# I2C_system.net
KiCad netlist of a schematic drawn in Altium Designer
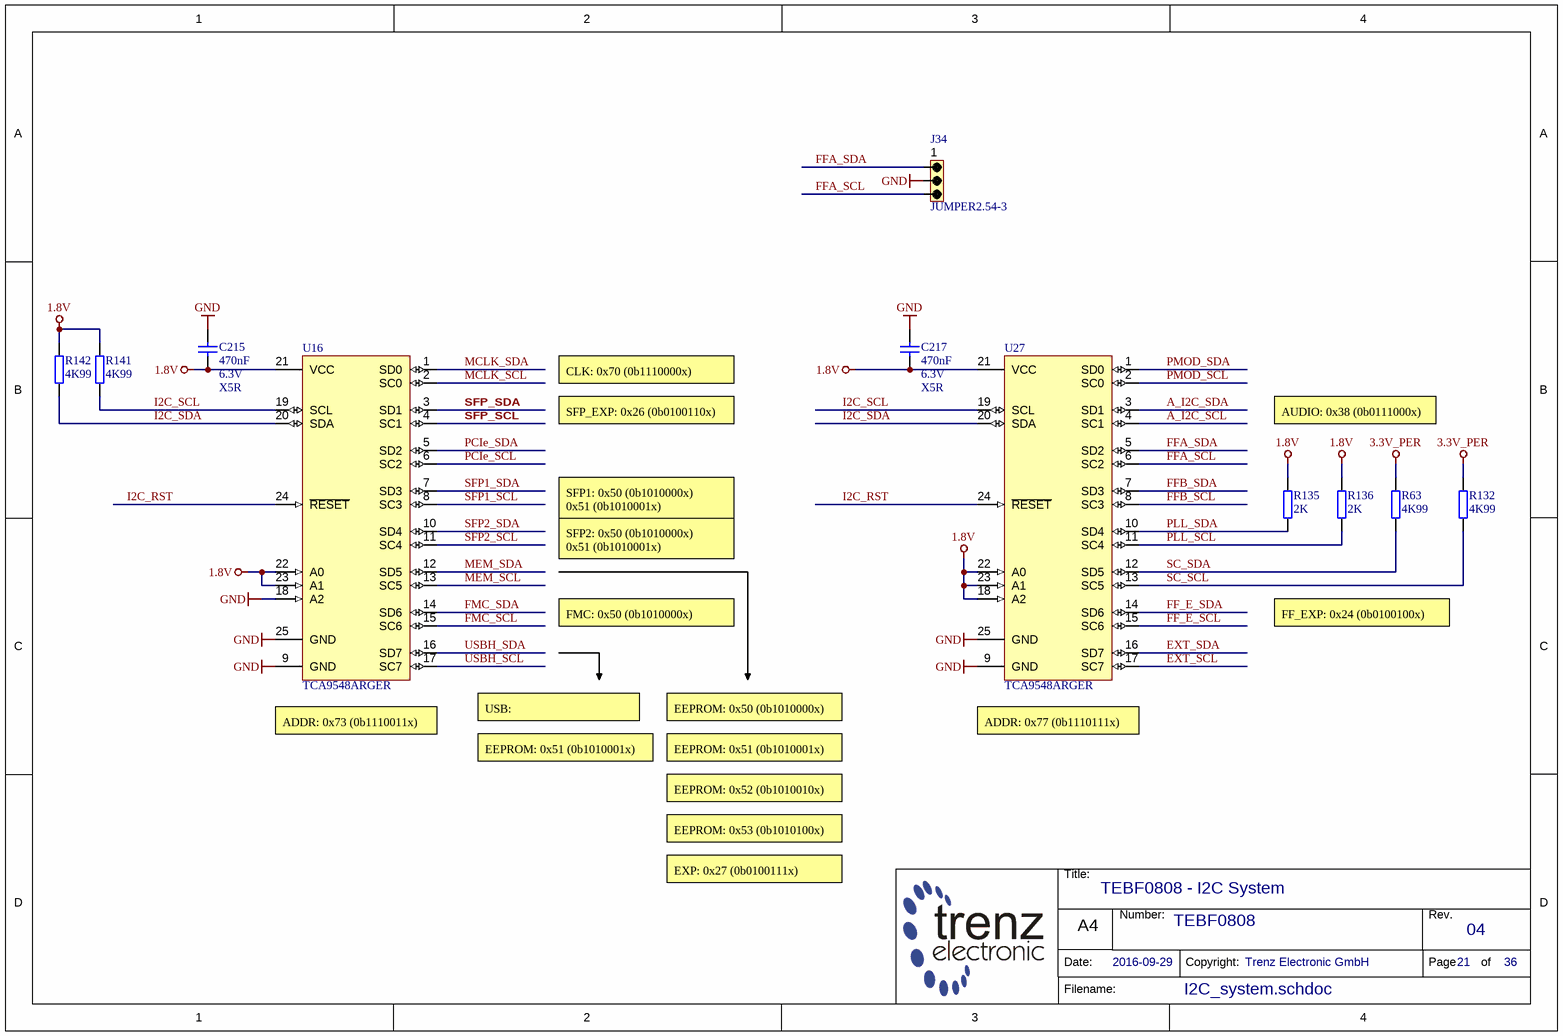
[diagram p0: I2C_system.schdoc]

(export (version "E")
  (design (tool "Eeschema 10.0.6"))
  (components
    (comp (ref "C215")
      (value "470nF")
      (footprint "CAPC1005X55N")
      (description "KON 470nF 6,3V X5R SMD")
      (fields (field (name "VOLTAGE") "6.3V") (field (name "TECHNOLOGY") "X5R"))
      (libsource (lib "TE") (part "CAP-NP"))
    )
    (comp (ref "C217")
      (value "470nF")
      (footprint "CAPC1005X55N")
      (description "KON 470nF 6,3V X5R SMD")
      (fields (field (name "VOLTAGE") "6.3V") (field (name "TECHNOLOGY") "X5R"))
      (libsource (lib "TE") (part "CAP-NP"))
    )
    (comp (ref "J34")
      (value "JUMPER2.54-3")
      (footprint "JUMPER2_54-3")
      (description "Stiftleiste gerade 1-reihig, 3pol.")
      (libsource (lib "TE") (part "JUMPER2.54-3"))
    )
    (comp (ref "R63")
      (value "4K99")
      (footprint "RESC1005X40N")
      (description "WID SMD 4K99 1% 0,063W")
      (fields (field (name "TOLERANCE") "1%"))
      (libsource (lib "TE") (part "RES"))
    )
    (comp (ref "R132")
      (value "4K99")
      (footprint "RESC1005X40N")
      (description "WID SMD 4K99 1% 0,063W")
      (fields (field (name "TOLERANCE") "1%"))
      (libsource (lib "TE") (part "RES"))
    )
    (comp (ref "R135")
      (value "2K")
      (footprint "RESC1005X40N")
      (description "WID SMD 2K 1% 0,063W")
      (fields (field (name "TOLERANCE") "1%"))
      (libsource (lib "TE") (part "RES"))
    )
    (comp (ref "R136")
      (value "2K")
      (footprint "RESC1005X40N")
      (description "WID SMD 2K 1% 0,063W")
      (fields (field (name "TOLERANCE") "1%"))
      (libsource (lib "TE") (part "RES"))
    )
    (comp (ref "R141")
      (value "4K99")
      (footprint "RESC1005X40N")
      (description "WID SMD 4K99 1% 0,063W")
      (fields (field (name "TOLERANCE") "1%"))
      (libsource (lib "TE") (part "RES"))
    )
    (comp (ref "R142")
      (value "4K99")
      (footprint "RESC1005X40N")
      (description "WID SMD 4K99 1% 0,063W")
      (fields (field (name "TOLERANCE") "1%"))
      (libsource (lib "TE") (part "RES"))
    )
    (comp (ref "U16")
      (value "TCA9548ARGER")
      (footprint "QFN50P400X400X100-25N-220")
      (libsource (lib "TE") (part "TCA9548ARGER"))
    )
    (comp (ref "U27")
      (value "TCA9548ARGER")
      (footprint "QFN50P400X400X100-25N-220")
      (libsource (lib "TE") (part "TCA9548ARGER"))
    )
  )
  (nets
    (net (code "1") (name "/A_I2C_SCL") (class "Default")
      (node (ref "U27") (pin "4") (pinfunction "SC1_4") (pintype "bidirectional"))
    )
    (net (code "2") (name "/A_I2C_SDA") (class "Default")
      (node (ref "U27") (pin "3") (pinfunction "SD1_3") (pintype "bidirectional"))
    )
    (net (code "3") (name "/EXT_SCL") (class "Default")
      (node (ref "U27") (pin "17") (pinfunction "SC7_17") (pintype "bidirectional"))
    )
    (net (code "4") (name "/EXT_SDA") (class "Default")
      (node (ref "U27") (pin "16") (pinfunction "SD7_16") (pintype "bidirectional"))
    )
    (net (code "5") (name "/FFA_SCL") (class "Default")
      (node (ref "J34") (pin "3") (pinfunction "3_3") (pintype "passive"))
      (node (ref "U27") (pin "6") (pinfunction "SC2_6") (pintype "bidirectional"))
    )
    (net (code "6") (name "/FFA_SDA") (class "Default")
      (node (ref "J34") (pin "1") (pinfunction "1_1") (pintype "passive"))
      (node (ref "U27") (pin "5") (pinfunction "SD2_5") (pintype "bidirectional"))
    )
    (net (code "7") (name "/FFB_SCL") (class "Default")
      (node (ref "U27") (pin "8") (pinfunction "SC3_8") (pintype "bidirectional"))
    )
    (net (code "8") (name "/FFB_SDA") (class "Default")
      (node (ref "U27") (pin "7") (pinfunction "SD3_7") (pintype "bidirectional"))
    )
    (net (code "9") (name "/FF_E_SCL") (class "Default")
      (node (ref "U27") (pin "15") (pinfunction "SC6_15") (pintype "bidirectional"))
    )
    (net (code "10") (name "/FF_E_SDA") (class "Default")
      (node (ref "U27") (pin "14") (pinfunction "SD6_14") (pintype "bidirectional"))
    )
    (net (code "11") (name "/FMC_SCL") (class "Default")
      (node (ref "U16") (pin "15") (pinfunction "SC6_15") (pintype "bidirectional"))
    )
    (net (code "12") (name "/FMC_SDA") (class "Default")
      (node (ref "U16") (pin "14") (pinfunction "SD6_14") (pintype "bidirectional"))
    )
    (net (code "13") (name "/I2C_RST") (class "Default")
      (node (ref "U16") (pin "24") (pinfunction "~{RESET}_24") (pintype "input"))
      (node (ref "U27") (pin "24") (pinfunction "~{RESET}_24") (pintype "input"))
    )
    (net (code "14") (name "/I2C_SCL") (class "Default")
      (node (ref "R141") (pin "2") (pinfunction "2_2") (pintype "passive"))
      (node (ref "U16") (pin "19") (pinfunction "SCL_19") (pintype "bidirectional"))
      (node (ref "U27") (pin "19") (pinfunction "SCL_19") (pintype "bidirectional"))
    )
    (net (code "15") (name "/I2C_SDA") (class "Default")
      (node (ref "R142") (pin "2") (pinfunction "2_2") (pintype "passive"))
      (node (ref "U16") (pin "20") (pinfunction "SDA_20") (pintype "bidirectional"))
      (node (ref "U27") (pin "20") (pinfunction "SDA_20") (pintype "bidirectional"))
    )
    (net (code "16") (name "/MCLK_SCL") (class "Default")
      (node (ref "U16") (pin "2") (pinfunction "SC0_2") (pintype "bidirectional"))
    )
    (net (code "17") (name "/MCLK_SDA") (class "Default")
      (node (ref "U16") (pin "1") (pinfunction "SD0_1") (pintype "bidirectional"))
    )
    (net (code "18") (name "/MEM_SCL") (class "Default")
      (node (ref "U16") (pin "13") (pinfunction "SC5_13") (pintype "bidirectional"))
    )
    (net (code "19") (name "/MEM_SDA") (class "Default")
      (node (ref "U16") (pin "12") (pinfunction "SD5_12") (pintype "bidirectional"))
    )
    (net (code "20") (name "/PCIe_SCL") (class "Default")
      (node (ref "U16") (pin "6") (pinfunction "SC2_6") (pintype "bidirectional"))
    )
    (net (code "21") (name "/PCIe_SDA") (class "Default")
      (node (ref "U16") (pin "5") (pinfunction "SD2_5") (pintype "bidirectional"))
    )
    (net (code "22") (name "/PLL_SCL") (class "Default")
      (node (ref "R136") (pin "1") (pinfunction "1_1") (pintype "passive"))
      (node (ref "U27") (pin "11") (pinfunction "SC4_11") (pintype "bidirectional"))
    )
    (net (code "23") (name "/PLL_SDA") (class "Default")
      (node (ref "R135") (pin "1") (pinfunction "1_1") (pintype "passive"))
      (node (ref "U27") (pin "10") (pinfunction "SD4_10") (pintype "bidirectional"))
    )
    (net (code "24") (name "/PMOD_SCL") (class "Default")
      (node (ref "U27") (pin "2") (pinfunction "SC0_2") (pintype "bidirectional"))
    )
    (net (code "25") (name "/PMOD_SDA") (class "Default")
      (node (ref "U27") (pin "1") (pinfunction "SD0_1") (pintype "bidirectional"))
    )
    (net (code "26") (name "/SC_SCL") (class "Default")
      (node (ref "R132") (pin "2") (pinfunction "2_2") (pintype "passive"))
      (node (ref "U27") (pin "13") (pinfunction "SC5_13") (pintype "bidirectional"))
    )
    (net (code "27") (name "/SC_SDA") (class "Default")
      (node (ref "R63") (pin "2") (pinfunction "2_2") (pintype "passive"))
      (node (ref "U27") (pin "12") (pinfunction "SD5_12") (pintype "bidirectional"))
    )
    (net (code "28") (name "/SFP1_SCL") (class "Default")
      (node (ref "U16") (pin "8") (pinfunction "SC3_8") (pintype "bidirectional"))
    )
    (net (code "29") (name "/SFP1_SDA") (class "Default")
      (node (ref "U16") (pin "7") (pinfunction "SD3_7") (pintype "bidirectional"))
    )
    (net (code "30") (name "/SFP2_SCL") (class "Default")
      (node (ref "U16") (pin "11") (pinfunction "SC4_11") (pintype "bidirectional"))
    )
    (net (code "31") (name "/SFP2_SDA") (class "Default")
      (node (ref "U16") (pin "10") (pinfunction "SD4_10") (pintype "bidirectional"))
    )
    (net (code "32") (name "/SFP_SCL") (class "Default")
      (node (ref "U16") (pin "4") (pinfunction "SC1_4") (pintype "bidirectional"))
    )
    (net (code "33") (name "/SFP_SDA") (class "Default")
      (node (ref "U16") (pin "3") (pinfunction "SD1_3") (pintype "bidirectional"))
    )
    (net (code "34") (name "/USBH_SCL") (class "Default")
      (node (ref "U16") (pin "17") (pinfunction "SC7_17") (pintype "bidirectional"))
    )
    (net (code "35") (name "/USBH_SDA") (class "Default")
      (node (ref "U16") (pin "16") (pinfunction "SD7_16") (pintype "bidirectional"))
    )
    (net (code "36") (name "1.8V") (class "Default")
      (node (ref "C215") (pin "2") (pinfunction "2_2") (pintype "passive"))
      (node (ref "C217") (pin "2") (pinfunction "2_2") (pintype "passive"))
      (node (ref "R135") (pin "2") (pinfunction "2_2") (pintype "passive"))
      (node (ref "R136") (pin "2") (pinfunction "2_2") (pintype "passive"))
      (node (ref "R141") (pin "1") (pinfunction "1_1") (pintype "passive"))
      (node (ref "R142") (pin "1") (pinfunction "1_1") (pintype "passive"))
      (node (ref "U16") (pin "21") (pinfunction "VCC_21") (pintype "power_in"))
      (node (ref "U16") (pin "22") (pinfunction "A0_22") (pintype "input"))
      (node (ref "U16") (pin "23") (pinfunction "A1_23") (pintype "input"))
      (node (ref "U27") (pin "18") (pinfunction "A2_18") (pintype "input"))
      (node (ref "U27") (pin "21") (pinfunction "VCC_21") (pintype "power_in"))
      (node (ref "U27") (pin "22") (pinfunction "A0_22") (pintype "input"))
      (node (ref "U27") (pin "23") (pinfunction "A1_23") (pintype "input"))
    )
    (net (code "37") (name "3.3V_PER") (class "Default")
      (node (ref "R132") (pin "1") (pinfunction "1_1") (pintype "passive"))
      (node (ref "R63") (pin "1") (pinfunction "1_1") (pintype "passive"))
    )
    (net (code "38") (name "GND") (class "Default")
      (node (ref "C215") (pin "1") (pinfunction "1_1") (pintype "passive"))
      (node (ref "C217") (pin "1") (pinfunction "1_1") (pintype "passive"))
      (node (ref "J34") (pin "2") (pinfunction "2_2") (pintype "passive"))
      (node (ref "U16") (pin "18") (pinfunction "A2_18") (pintype "input"))
      (node (ref "U16") (pin "25") (pinfunction "GND_25") (pintype "power_in"))
      (node (ref "U16") (pin "9") (pinfunction "GND_9") (pintype "power_in"))
      (node (ref "U27") (pin "25") (pinfunction "GND_25") (pintype "power_in"))
      (node (ref "U27") (pin "9") (pinfunction "GND_9") (pintype "power_in"))
    )
  )
)
